# EPS.net
KiCad netlist of a schematic drawn in EAGLE
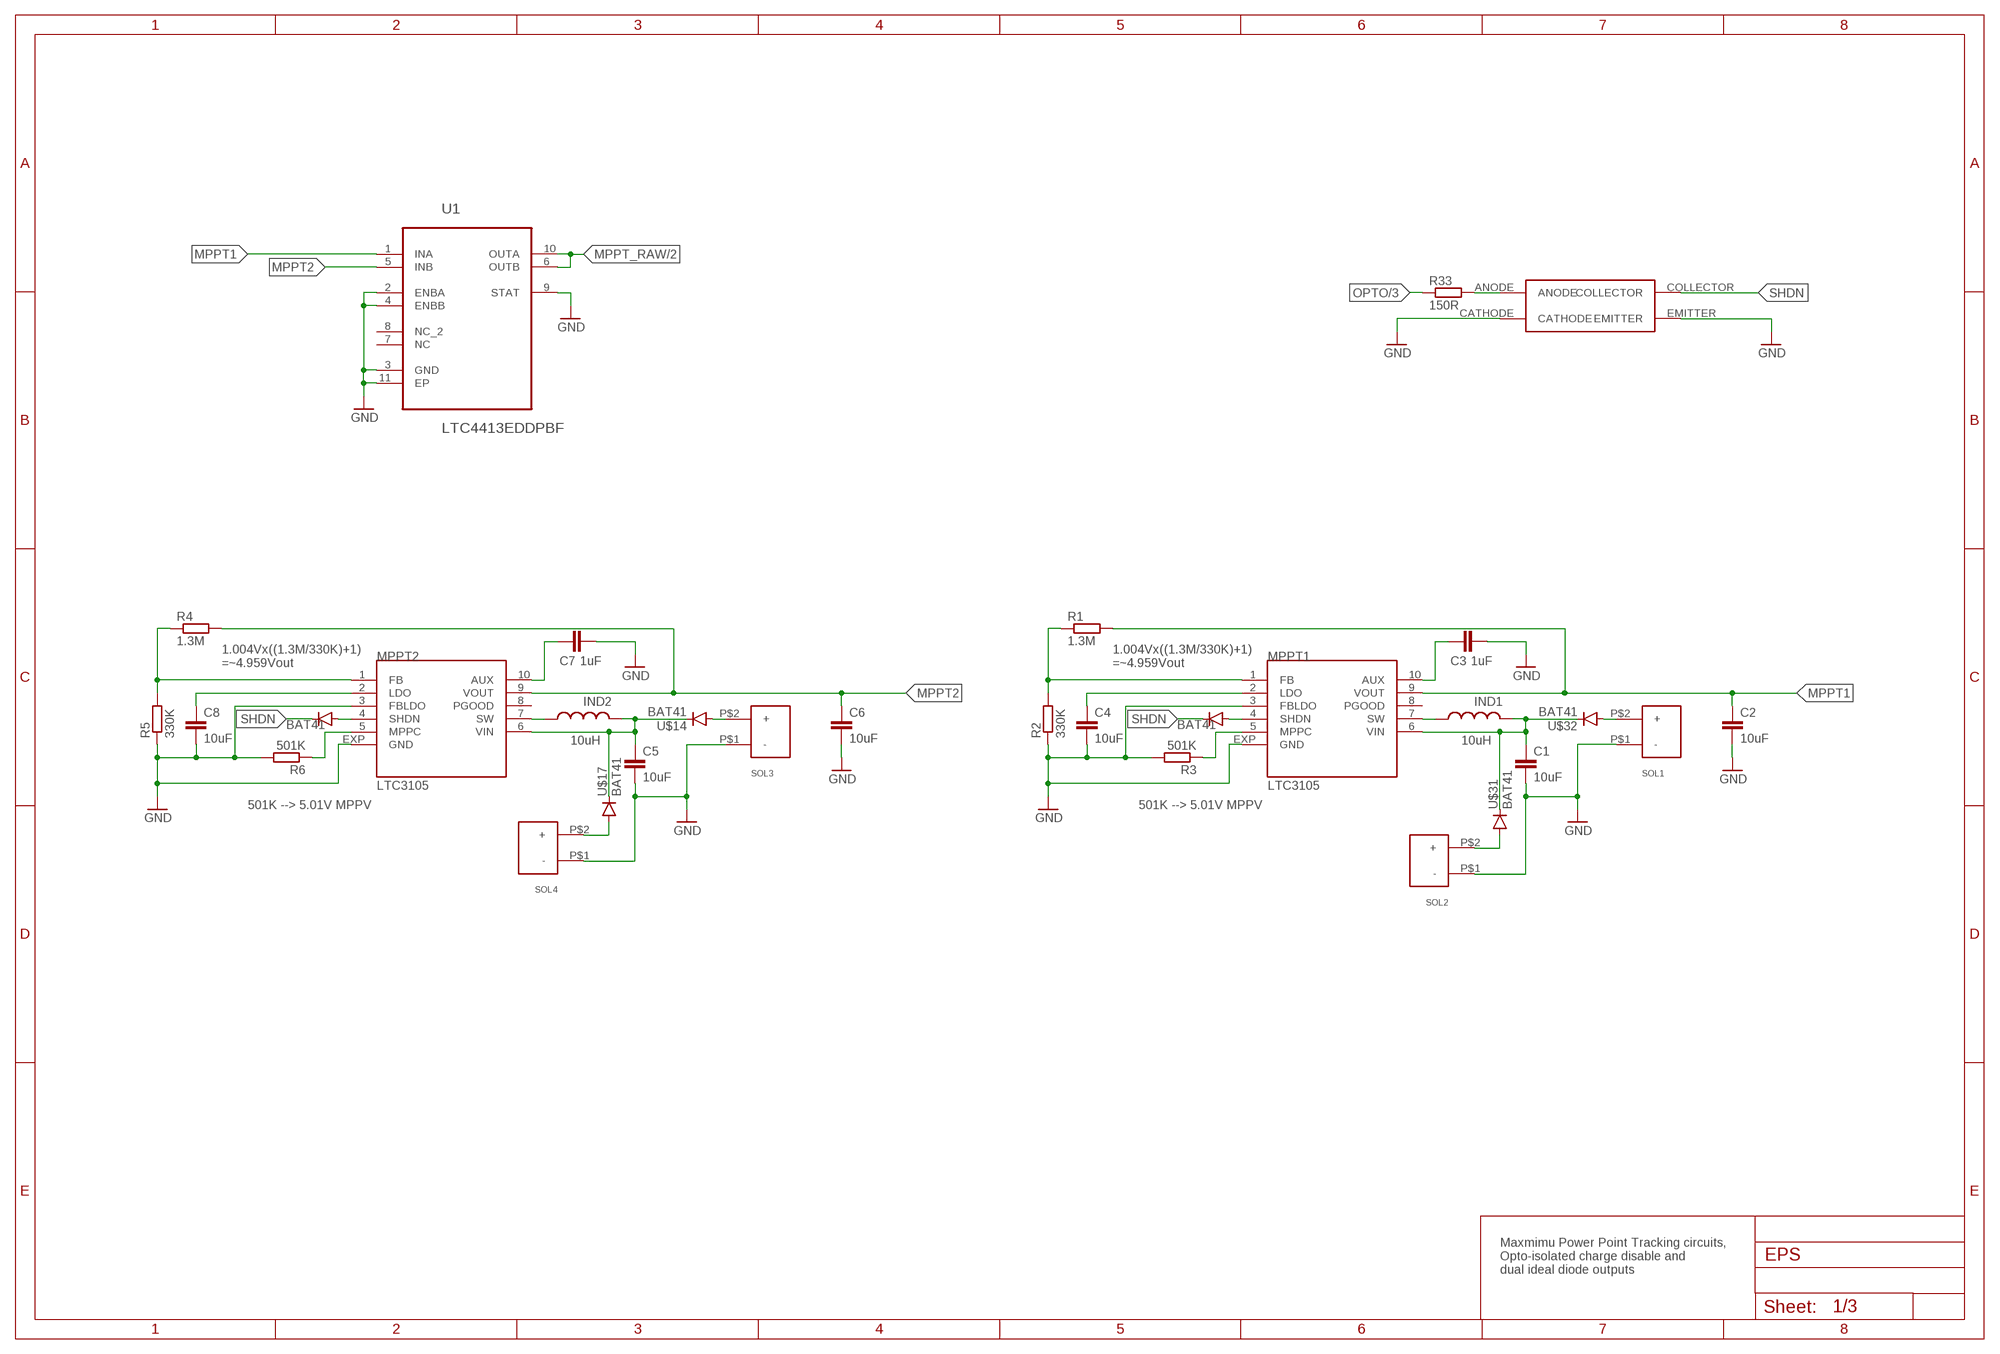
[diagram p0: schematic, sheet 1]
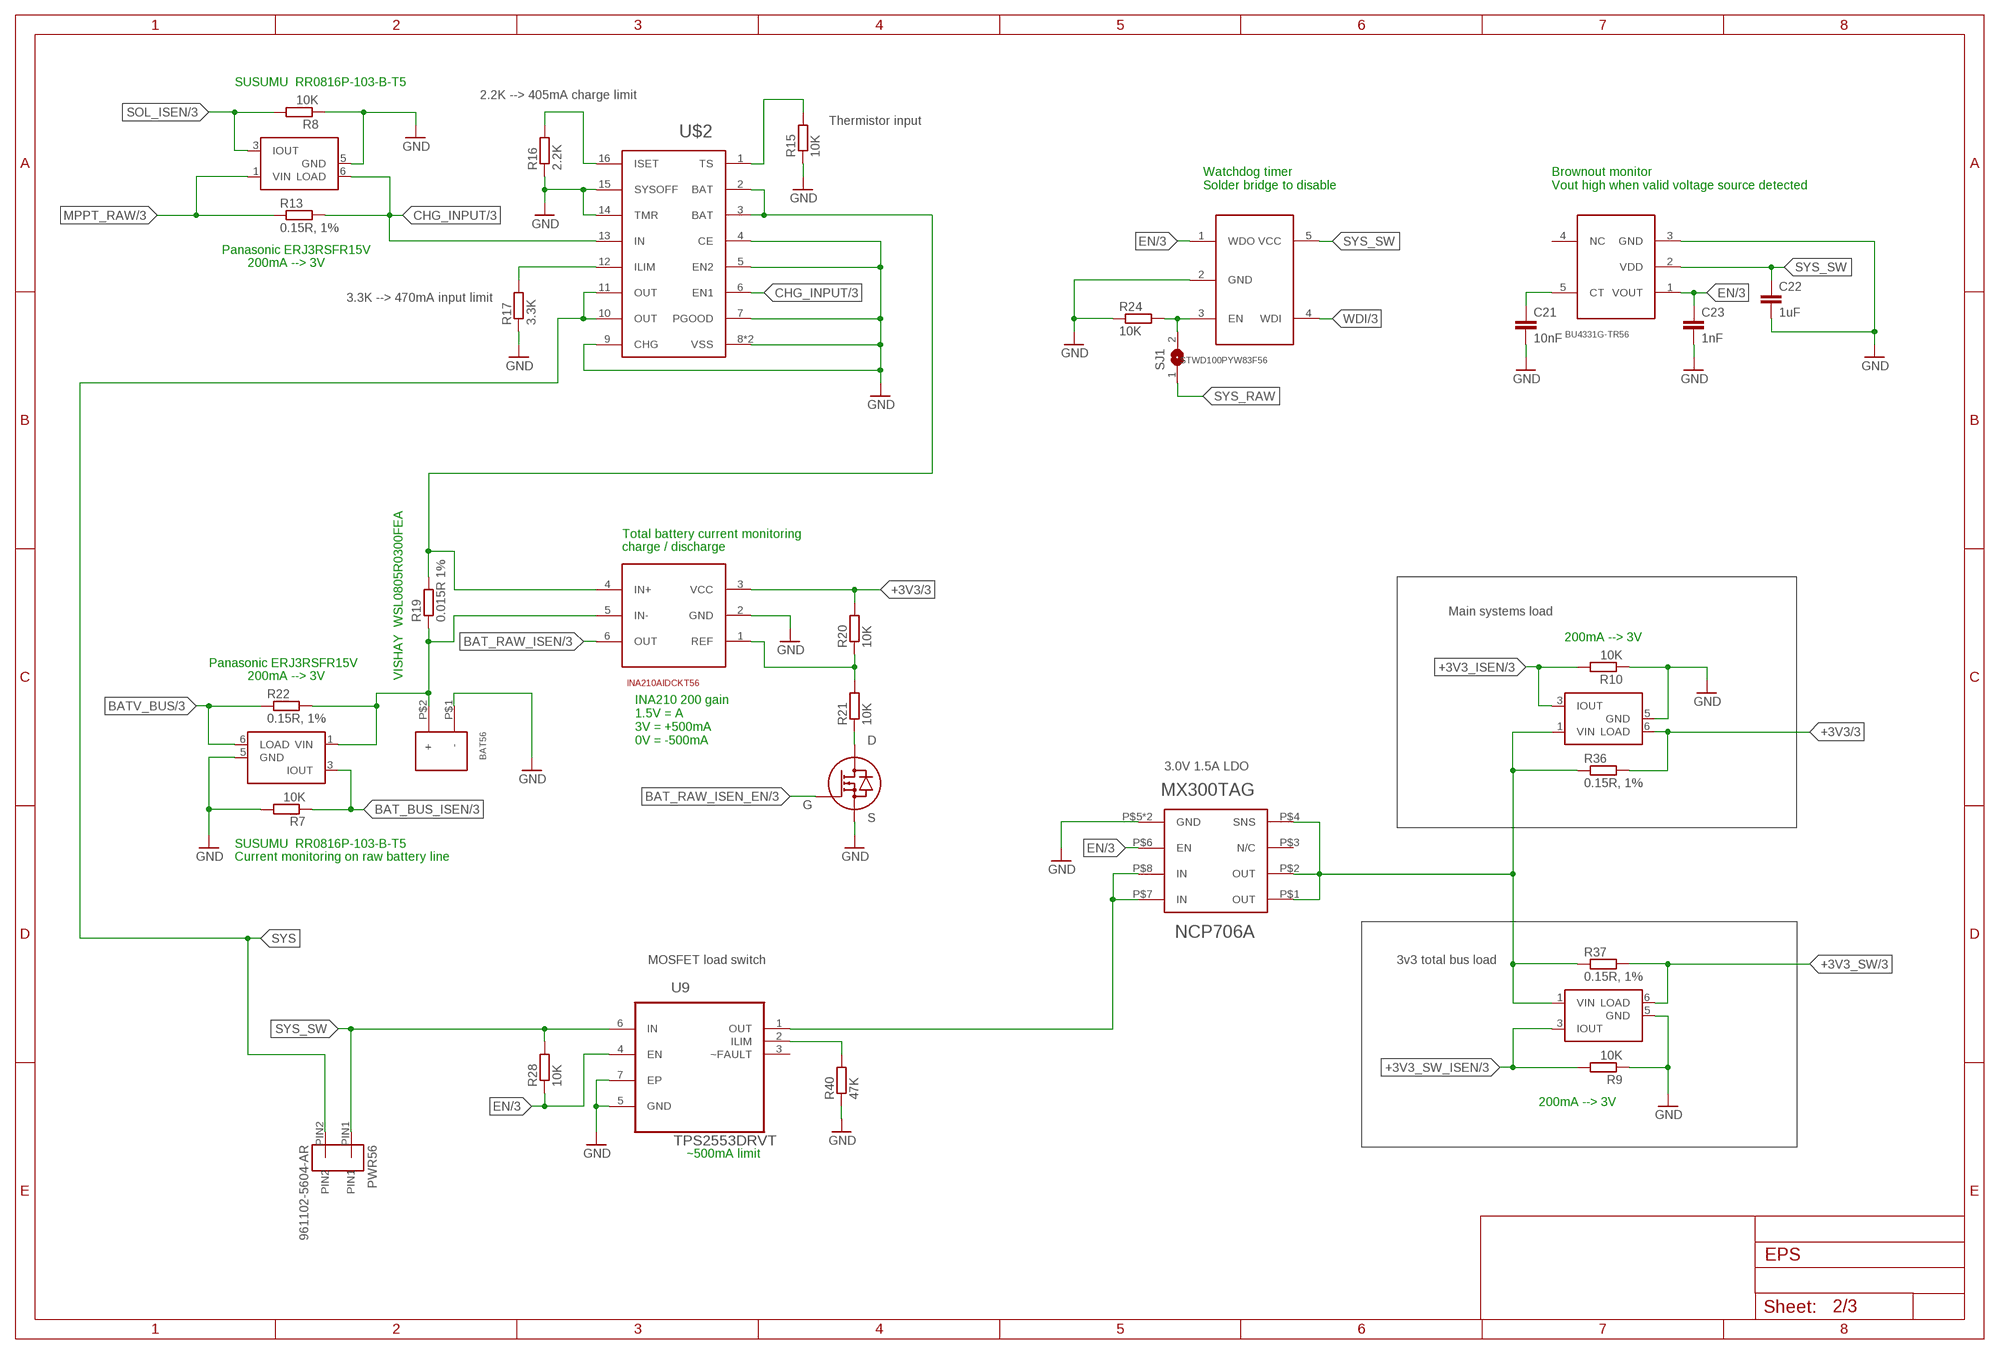
[diagram p1: schematic, sheet 2]
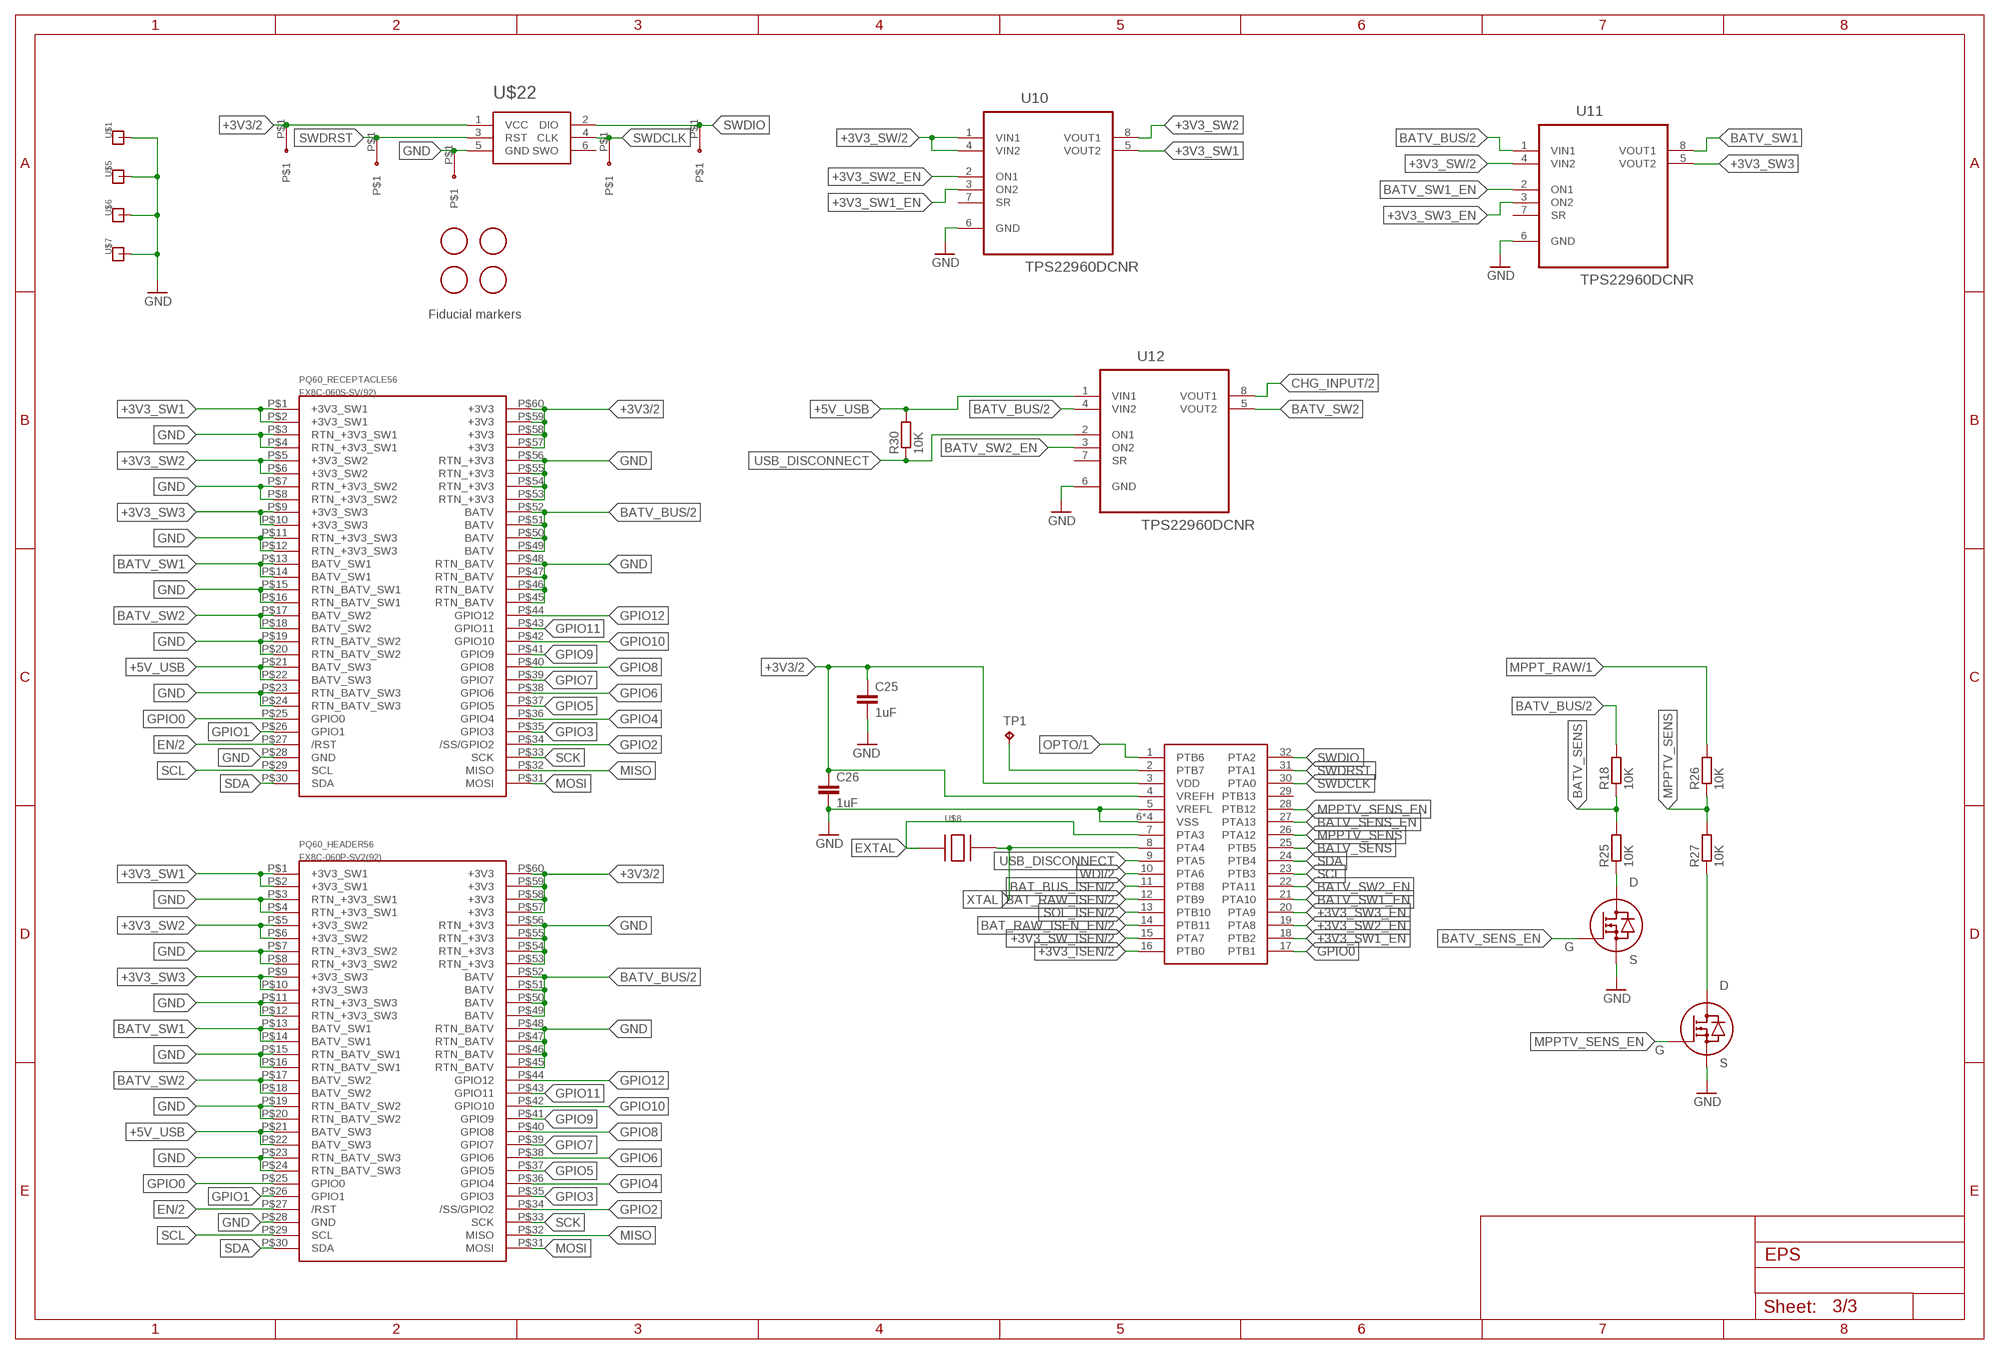
[diagram p2: schematic, sheet 3]

(export (version "E")
  (design (tool "Eeschema 10.0.6"))
  (components
    (comp (ref "C1")
      (value "10uF")
      (footprint "eagle-import:C0603")
      (libsource (lib "eagle-import") (part "C-EUC0603"))
    )
    (comp (ref "C2")
      (value "10uF")
      (footprint "eagle-import:C0603")
      (libsource (lib "eagle-import") (part "C-EUC0603"))
    )
    (comp (ref "C3")
      (value "1uF")
      (footprint "eagle-import:C0402")
      (libsource (lib "eagle-import") (part "C-EUC0402"))
    )
    (comp (ref "C4")
      (value "10uF")
      (footprint "eagle-import:C0603")
      (libsource (lib "eagle-import") (part "C-EUC0603"))
    )
    (comp (ref "C5")
      (value "10uF")
      (footprint "eagle-import:C0603")
      (libsource (lib "eagle-import") (part "C-EUC0603"))
    )
    (comp (ref "C6")
      (value "10uF")
      (footprint "eagle-import:C0603")
      (libsource (lib "eagle-import") (part "C-EUC0603"))
    )
    (comp (ref "C7")
      (value "1uF")
      (footprint "eagle-import:C0402")
      (libsource (lib "eagle-import") (part "C-EUC0402"))
    )
    (comp (ref "C8")
      (value "10uF")
      (footprint "eagle-import:C0603")
      (libsource (lib "eagle-import") (part "C-EUC0603"))
    )
    (comp (ref "IND1")
      (value "WE-TPC-744031100")
      (footprint "eagle-import:WE-TPC-744031100")
      (libsource (lib "eagle-import") (part "WE-TPC-744031100"))
    )
    (comp (ref "IND2")
      (value "WE-TPC-744031100")
      (footprint "eagle-import:WE-TPC-744031100")
      (libsource (lib "eagle-import") (part "WE-TPC-744031100"))
    )
    (comp (ref "MPPT1")
      (value "LTC3105")
      (footprint "eagle-import:DFN-3X3")
      (libsource (lib "eagle-import") (part "LTC3105"))
    )
    (comp (ref "MPPT2")
      (value "LTC3105")
      (footprint "eagle-import:DFN-3X3")
      (libsource (lib "eagle-import") (part "LTC3105"))
    )
    (comp (ref "R1")
      (value "1.3M")
      (footprint "eagle-import:R0402")
      (libsource (lib "eagle-import") (part "R-EU_R0402"))
    )
    (comp (ref "R2")
      (value "330K")
      (footprint "eagle-import:R0402")
      (libsource (lib "eagle-import") (part "R-EU_R0402"))
    )
    (comp (ref "R3")
      (value "501K")
      (footprint "eagle-import:R0402")
      (libsource (lib "eagle-import") (part "R-EU_R0402"))
    )
    (comp (ref "R4")
      (value "1.3M")
      (footprint "eagle-import:R0402")
      (libsource (lib "eagle-import") (part "R-EU_R0402"))
    )
    (comp (ref "R5")
      (value "330K")
      (footprint "eagle-import:R0402")
      (libsource (lib "eagle-import") (part "R-EU_R0402"))
    )
    (comp (ref "R6")
      (value "501K")
      (footprint "eagle-import:R0402")
      (libsource (lib "eagle-import") (part "R-EU_R0402"))
    )
    (comp (ref "R33")
      (value "150R")
      (footprint "eagle-import:R0402")
      (libsource (lib "eagle-import") (part "R-EU_R0402"))
    )
    (comp (ref "SOL1")
      (value "JST-B2B-ZH")
      (footprint "eagle-import:JST-B2B-ZR")
      (libsource (lib "eagle-import") (part "JST-B2B-ZH"))
    )
    (comp (ref "SOL2")
      (value "JST-B2B-ZH")
      (footprint "eagle-import:JST-B2B-ZR")
      (libsource (lib "eagle-import") (part "JST-B2B-ZH"))
    )
    (comp (ref "SOL3")
      (value "JST-B2B-ZH")
      (footprint "eagle-import:JST-B2B-ZR")
      (libsource (lib "eagle-import") (part "JST-B2B-ZH"))
    )
    (comp (ref "SOL4")
      (value "JST-B2B-ZH")
      (footprint "eagle-import:JST-B2B-ZR")
      (libsource (lib "eagle-import") (part "JST-B2B-ZH"))
    )
    (comp (ref "U$4")
      (value "BAT41")
      (footprint "eagle-import:SOD-123")
      (libsource (lib "eagle-import") (part "BAT41"))
    )
    (comp (ref "U$10")
      (value "BAT41")
      (footprint "eagle-import:SOD-123")
      (libsource (lib "eagle-import") (part "BAT41"))
    )
    (comp (ref "U$14")
      (value "BAT41")
      (footprint "eagle-import:SOD-123")
      (libsource (lib "eagle-import") (part "BAT41"))
    )
    (comp (ref "U$17")
      (value "BAT41")
      (footprint "eagle-import:SOD-123")
      (libsource (lib "eagle-import") (part "BAT41"))
    )
    (comp (ref "U$24")
      (value "EL3H7")
      (footprint "eagle-import:EL3H7")
      (libsource (lib "eagle-import") (part "EL3H7"))
    )
    (comp (ref "U$31")
      (value "BAT41")
      (footprint "eagle-import:SOD-123")
      (libsource (lib "eagle-import") (part "BAT41"))
    )
    (comp (ref "U$32")
      (value "BAT41")
      (footprint "eagle-import:SOD-123")
      (libsource (lib "eagle-import") (part "BAT41"))
    )
    (comp (ref "U1")
      (value "LTC4413EDDPBF")
      (footprint "eagle-import:DFN300X300X80-11N")
      (fields (field (name "MPN") "LTC4413EDD#PBF"))
      (libsource (lib "eagle-import") (part "LTC4413EDDPBF"))
    )
    (comp (ref "C25")
      (value "1uF")
      (footprint "eagle-import:C0402")
      (libsource (lib "eagle-import") (part "C-EUC0402"))
    )
    (comp (ref "C26")
      (value "1uF")
      (footprint "eagle-import:C0402")
      (libsource (lib "eagle-import") (part "C-EUC0402"))
    )
    (comp (ref "FD1")
      (value "FIDUCIAL")
      (footprint "eagle-import:FIDUCIAL_1MM")
      (libsource (lib "eagle-import") (part "FIDUCIAL"))
    )
    (comp (ref "FD2")
      (value "FIDUCIAL")
      (footprint "eagle-import:FIDUCIAL_1MM")
      (libsource (lib "eagle-import") (part "FIDUCIAL"))
    )
    (comp (ref "FD3")
      (value "FIDUCIAL")
      (footprint "eagle-import:FIDUCIAL_1MM")
      (libsource (lib "eagle-import") (part "FIDUCIAL"))
    )
    (comp (ref "FD4")
      (value "FIDUCIAL")
      (footprint "eagle-import:FIDUCIAL_1MM")
      (libsource (lib "eagle-import") (part "FIDUCIAL"))
    )
    (comp (ref "PQ60_HEADER56")
      (value "FX8C-060P-SV2(92)")
      (footprint "eagle-import:FX8C-060P-SV(92)")
      (libsource (lib "eagle-import") (part "FX8C-060P-SV2(92)"))
    )
    (comp (ref "PQ60_RECEPTACLE56")
      (value "FX8C-060S-SV(92)")
      (footprint "eagle-import:FX8C-060S-SV(92)")
      (libsource (lib "eagle-import") (part "FX8C-060S-SV(92)"))
    )
    (comp (ref "R18")
      (value "10K")
      (footprint "eagle-import:R0402")
      (libsource (lib "eagle-import") (part "R-EU_R0402"))
    )
    (comp (ref "R25")
      (value "10K")
      (footprint "eagle-import:R0402")
      (libsource (lib "eagle-import") (part "R-EU_R0402"))
    )
    (comp (ref "R26")
      (value "10K")
      (footprint "eagle-import:R0402")
      (libsource (lib "eagle-import") (part "R-EU_R0402"))
    )
    (comp (ref "R27")
      (value "10K")
      (footprint "eagle-import:R0402")
      (libsource (lib "eagle-import") (part "R-EU_R0402"))
    )
    (comp (ref "R30")
      (value "10K")
      (footprint "eagle-import:R0402")
      (libsource (lib "eagle-import") (part "R-EU_R0402"))
    )
    (comp (ref "TP1")
      (value "TPTP07R")
      (footprint "eagle-import:TP07R")
      (libsource (lib "eagle-import") (part "TPTP07R"))
    )
    (comp (ref "U$1")
      (value "3MMPILAR")
      (footprint "eagle-import:3MMPILAR")
      (libsource (lib "eagle-import") (part "3MMPILAR"))
    )
    (comp (ref "U$3")
      (value "DEBUG-TP")
      (footprint "eagle-import:DEBUG-TP")
      (libsource (lib "eagle-import") (part "DEBUG-TP"))
    )
    (comp (ref "U$5")
      (value "3MMPILAR")
      (footprint "eagle-import:3MMPILAR")
      (libsource (lib "eagle-import") (part "3MMPILAR"))
    )
    (comp (ref "U$6")
      (value "3MMPILAR")
      (footprint "eagle-import:3MMPILAR")
      (libsource (lib "eagle-import") (part "3MMPILAR"))
    )
    (comp (ref "U$7")
      (value "3MMPILAR")
      (footprint "eagle-import:3MMPILAR")
      (libsource (lib "eagle-import") (part "3MMPILAR"))
    )
    (comp (ref "U$8")
      (value "ABS25_32.768KHZ")
      (footprint "eagle-import:ABS25")
      (libsource (lib "eagle-import") (part "ABS25_32.768KHZ"))
    )
    (comp (ref "U$11")
      (value "PMV40UN2")
      (footprint "eagle-import:SOT23-3")
      (libsource (lib "eagle-import") (part "PMV40UN2"))
    )
    (comp (ref "U$12")
      (value "PMV40UN2")
      (footprint "eagle-import:SOT23-3")
      (libsource (lib "eagle-import") (part "PMV40UN2"))
    )
    (comp (ref "U$16")
      (value "DEBUG-TP")
      (footprint "eagle-import:DEBUG-TP")
      (libsource (lib "eagle-import") (part "DEBUG-TP"))
    )
    (comp (ref "U$21")
      (value "MKL02Z16VFM4")
      (footprint "eagle-import:MKL02Z16VFM4")
      (libsource (lib "eagle-import") (part "MKL02Z16VFM4"))
    )
    (comp (ref "U$22")
      (value "TAG_CONNECT")
      (footprint "eagle-import:TAG_CONNECT")
      (libsource (lib "eagle-import") (part "TAG_CONNECT"))
    )
    (comp (ref "U$23")
      (value "DEBUG-TP")
      (footprint "eagle-import:DEBUG-TP")
      (libsource (lib "eagle-import") (part "DEBUG-TP"))
    )
    (comp (ref "U$27")
      (value "DEBUG-TP")
      (footprint "eagle-import:DEBUG-TP")
      (libsource (lib "eagle-import") (part "DEBUG-TP"))
    )
    (comp (ref "U$28")
      (value "DEBUG-TP")
      (footprint "eagle-import:DEBUG-TP")
      (libsource (lib "eagle-import") (part "DEBUG-TP"))
    )
    (comp (ref "U10")
      (value "TPS22960DCNR")
      (footprint "eagle-import:SOT65P280X145-8N")
      (libsource (lib "eagle-import") (part "TPS22960DCNR"))
    )
    (comp (ref "U11")
      (value "TPS22960DCNR")
      (footprint "eagle-import:SOT65P280X145-8N")
      (libsource (lib "eagle-import") (part "TPS22960DCNR"))
    )
    (comp (ref "U12")
      (value "TPS22960DCNR")
      (footprint "eagle-import:SOT65P280X145-8N")
      (libsource (lib "eagle-import") (part "TPS22960DCNR"))
    )
    (comp (ref "BAT56")
      (value "JST-B2B-ZH")
      (footprint "eagle-import:JST-B2B-ZR")
      (libsource (lib "eagle-import") (part "JST-B2B-ZH"))
    )
    (comp (ref "BU4331G-TR56")
      (value "BU4231G-TR")
      (footprint "eagle-import:SSOP5")
      (libsource (lib "eagle-import") (part "BU4231G-TR"))
    )
    (comp (ref "C21")
      (value "10nF")
      (footprint "eagle-import:C0402")
      (libsource (lib "eagle-import") (part "C-EUC0402"))
    )
    (comp (ref "C22")
      (value "1uF")
      (footprint "eagle-import:C0402")
      (libsource (lib "eagle-import") (part "C-EUC0402"))
    )
    (comp (ref "C23")
      (value "1nF")
      (footprint "eagle-import:C0402")
      (libsource (lib "eagle-import") (part "C-EUC0402"))
    )
    (comp (ref "INA210AIDCKT56")
      (value "INA211A")
      (footprint "eagle-import:SC-70")
      (libsource (lib "eagle-import") (part "INA211A"))
    )
    (comp (ref "PWR56")
      (value "961102-5604-AR")
      (footprint "eagle-import:961102-5604-AR")
      (libsource (lib "eagle-import") (part "961102-5604-AR"))
    )
    (comp (ref "R7")
      (value "10K")
      (footprint "eagle-import:R0402")
      (libsource (lib "eagle-import") (part "R-EU_R0402"))
    )
    (comp (ref "R8")
      (value "10K")
      (footprint "eagle-import:R0402")
      (libsource (lib "eagle-import") (part "R-EU_R0402"))
    )
    (comp (ref "R9")
      (value "10K")
      (footprint "eagle-import:R0402")
      (libsource (lib "eagle-import") (part "R-EU_R0402"))
    )
    (comp (ref "R10")
      (value "10K")
      (footprint "eagle-import:R0402")
      (libsource (lib "eagle-import") (part "R-EU_R0402"))
    )
    (comp (ref "R13")
      (value "0.15R, 1%")
      (footprint "eagle-import:R0603")
      (libsource (lib "eagle-import") (part "R-EU_R0603"))
    )
    (comp (ref "R15")
      (value "10K")
      (footprint "eagle-import:R0402")
      (libsource (lib "eagle-import") (part "R-EU_R0402"))
    )
    (comp (ref "R16")
      (value "2.2K")
      (footprint "eagle-import:R0402")
      (libsource (lib "eagle-import") (part "R-EU_R0402"))
    )
    (comp (ref "R17")
      (value "3.3K")
      (footprint "eagle-import:R0402")
      (libsource (lib "eagle-import") (part "R-EU_R0402"))
    )
    (comp (ref "R19")
      (value "0.015R 1%")
      (footprint "eagle-import:R0603")
      (libsource (lib "eagle-import") (part "R-EU_R0603"))
    )
    (comp (ref "R20")
      (value "10K")
      (footprint "eagle-import:R0402")
      (libsource (lib "eagle-import") (part "R-EU_R0402"))
    )
    (comp (ref "R21")
      (value "10K")
      (footprint "eagle-import:R0402")
      (libsource (lib "eagle-import") (part "R-EU_R0402"))
    )
    (comp (ref "R22")
      (value "0.15R, 1%")
      (footprint "eagle-import:R0603")
      (libsource (lib "eagle-import") (part "R-EU_R0603"))
    )
    (comp (ref "R24")
      (value "10K")
      (footprint "eagle-import:R0402")
      (libsource (lib "eagle-import") (part "R-EU_R0402"))
    )
    (comp (ref "R28")
      (value "10K")
      (footprint "eagle-import:R0402")
      (libsource (lib "eagle-import") (part "R-EU_R0402"))
    )
    (comp (ref "R36")
      (value "0.15R, 1%")
      (footprint "eagle-import:R0603")
      (libsource (lib "eagle-import") (part "R-EU_R0603"))
    )
    (comp (ref "R37")
      (value "0.15R, 1%")
      (footprint "eagle-import:R0603")
      (libsource (lib "eagle-import") (part "R-EU_R0603"))
    )
    (comp (ref "R40")
      (value "47K")
      (footprint "eagle-import:R0402")
      (libsource (lib "eagle-import") (part "R-EU_R0402"))
    )
    (comp (ref "SJ1") (value "SJ") (footprint "eagle-import:SJ") (libsource (lib "eagle-import") (part "SJ")))
    (comp (ref "STWD100PYW83F56")
      (value "STWD100PYW83F")
      (footprint "eagle-import:SOT_323-5")
      (libsource (lib "eagle-import") (part "STWD100PYW83F"))
    )
    (comp (ref "U$2")
      (value "BQ24079")
      (footprint "eagle-import:PVQFN16-THERM")
      (libsource (lib "eagle-import") (part "BQ24079"))
    )
    (comp (ref "U$15")
      (value "PMV40UN2")
      (footprint "eagle-import:SOT23-3")
      (libsource (lib "eagle-import") (part "PMV40UN2"))
    )
    (comp (ref "U$18")
      (value "FAN4010IL6X_F113")
      (footprint "eagle-import:FAN4010IL6X_F113")
      (libsource (lib "eagle-import") (part "FAN4010IL6X_F113"))
    )
    (comp (ref "U$19")
      (value "FAN4010IL6X_F113")
      (footprint "eagle-import:FAN4010IL6X_F113")
      (libsource (lib "eagle-import") (part "FAN4010IL6X_F113"))
    )
    (comp (ref "U$20")
      (value "NCP706AMX300TAG")
      (footprint "eagle-import:XDFN8")
      (libsource (lib "eagle-import") (part "NCP706AMX300TAG"))
    )
    (comp (ref "U$25")
      (value "FAN4010IL6X_F113")
      (footprint "eagle-import:FAN4010IL6X_F113")
      (libsource (lib "eagle-import") (part "FAN4010IL6X_F113"))
    )
    (comp (ref "U$26")
      (value "FAN4010IL6X_F113")
      (footprint "eagle-import:FAN4010IL6X_F113")
      (libsource (lib "eagle-import") (part "FAN4010IL6X_F113"))
    )
    (comp (ref "U9")
      (value "TPS2553DRVT")
      (footprint "eagle-import:SON65P200X200X80-7N")
      (libsource (lib "eagle-import") (part "TPS2553DRVT"))
    )
  )
  (nets
    (net (code "1") (name "+3V3") (class "Default")
      (node (ref "C25") (pin "1") (pinfunction "1_1") (pintype "passive"))
      (node (ref "C26") (pin "1") (pinfunction "1_1") (pintype "passive"))
      (node (ref "INA210AIDCKT56") (pin "3") (pinfunction "VCC_3") (pintype "bidirectional"))
      (node (ref "PQ60_HEADER56") (pin "P$57") (pinfunction "+3V3_P$57") (pintype "power_in"))
      (node (ref "PQ60_HEADER56") (pin "P$58") (pinfunction "+3V3_P$58") (pintype "power_in"))
      (node (ref "PQ60_HEADER56") (pin "P$59") (pinfunction "+3V3_P$59") (pintype "power_in"))
      (node (ref "PQ60_HEADER56") (pin "P$60") (pinfunction "+3V3_P$60") (pintype "power_in"))
      (node (ref "PQ60_RECEPTACLE56") (pin "P$57") (pinfunction "+3V3_P$57") (pintype "power_in"))
      (node (ref "PQ60_RECEPTACLE56") (pin "P$58") (pinfunction "+3V3_P$58") (pintype "power_in"))
      (node (ref "PQ60_RECEPTACLE56") (pin "P$59") (pinfunction "+3V3_P$59") (pintype "power_in"))
      (node (ref "PQ60_RECEPTACLE56") (pin "P$60") (pinfunction "+3V3_P$60") (pintype "power_in"))
      (node (ref "R20") (pin "2") (pinfunction "2_2") (pintype "passive"))
      (node (ref "R36") (pin "2") (pinfunction "2_2") (pintype "passive"))
      (node (ref "U$21") (pin "3") (pinfunction "VDD_3") (pintype "bidirectional"))
      (node (ref "U$21") (pin "4") (pinfunction "VREFH_4") (pintype "bidirectional"))
      (node (ref "U$22") (pin "1") (pinfunction "VCC_1") (pintype "bidirectional"))
      (node (ref "U$25") (pin "6") (pinfunction "LOAD_6") (pintype "bidirectional"))
      (node (ref "U$3") (pin "P$1") (pinfunction "P$1_P$1") (pintype "bidirectional"))
    )
    (net (code "2") (name "+3V3_ISEN") (class "Default")
      (node (ref "R10") (pin "2") (pinfunction "2_2") (pintype "passive"))
      (node (ref "U$21") (pin "16") (pinfunction "PTB0_16") (pintype "bidirectional"))
      (node (ref "U$25") (pin "3") (pinfunction "IOUT_3") (pintype "bidirectional"))
    )
    (net (code "3") (name "+3V3_SW") (class "Default")
      (node (ref "R37") (pin "2") (pinfunction "2_2") (pintype "passive"))
      (node (ref "U$26") (pin "6") (pinfunction "LOAD_6") (pintype "bidirectional"))
      (node (ref "U10") (pin "1") (pinfunction "VIN1_1") (pintype "power_in"))
      (node (ref "U10") (pin "4") (pinfunction "VIN2_4") (pintype "power_in"))
      (node (ref "U11") (pin "4") (pinfunction "VIN2_4") (pintype "power_in"))
    )
    (net (code "4") (name "+3V3_SW1") (class "Default")
      (node (ref "PQ60_HEADER56") (pin "P$1") (pinfunction "+3V3_SW1_P$1") (pintype "power_in"))
      (node (ref "PQ60_HEADER56") (pin "P$2") (pinfunction "+3V3_SW1_P$2") (pintype "power_in"))
      (node (ref "PQ60_RECEPTACLE56") (pin "P$1") (pinfunction "+3V3_SW1_P$1") (pintype "power_in"))
      (node (ref "PQ60_RECEPTACLE56") (pin "P$2") (pinfunction "+3V3_SW1_P$2") (pintype "power_in"))
      (node (ref "U10") (pin "5") (pinfunction "VOUT2_5") (pintype "output"))
    )
    (net (code "5") (name "+3V3_SW1_EN") (class "Default")
      (node (ref "U$21") (pin "18") (pinfunction "PTB2_18") (pintype "bidirectional"))
      (node (ref "U10") (pin "3") (pinfunction "ON2_3") (pintype "input"))
    )
    (net (code "6") (name "+3V3_SW2") (class "Default")
      (node (ref "PQ60_HEADER56") (pin "P$5") (pinfunction "+3V3_SW2_P$5") (pintype "power_in"))
      (node (ref "PQ60_HEADER56") (pin "P$6") (pinfunction "+3V3_SW2_P$6") (pintype "power_in"))
      (node (ref "PQ60_RECEPTACLE56") (pin "P$5") (pinfunction "+3V3_SW2_P$5") (pintype "power_in"))
      (node (ref "PQ60_RECEPTACLE56") (pin "P$6") (pinfunction "+3V3_SW2_P$6") (pintype "power_in"))
      (node (ref "U10") (pin "8") (pinfunction "VOUT1_8") (pintype "output"))
    )
    (net (code "7") (name "+3V3_SW2_EN") (class "Default")
      (node (ref "U$21") (pin "19") (pinfunction "PTA8_19") (pintype "bidirectional"))
      (node (ref "U10") (pin "2") (pinfunction "ON1_2") (pintype "input"))
    )
    (net (code "8") (name "+3V3_SW3") (class "Default")
      (node (ref "PQ60_HEADER56") (pin "P$10") (pinfunction "+3V3_SW3_P$10") (pintype "power_in"))
      (node (ref "PQ60_HEADER56") (pin "P$9") (pinfunction "+3V3_SW3_P$9") (pintype "power_in"))
      (node (ref "PQ60_RECEPTACLE56") (pin "P$10") (pinfunction "+3V3_SW3_P$10") (pintype "power_in"))
      (node (ref "PQ60_RECEPTACLE56") (pin "P$9") (pinfunction "+3V3_SW3_P$9") (pintype "power_in"))
      (node (ref "U11") (pin "5") (pinfunction "VOUT2_5") (pintype "output"))
    )
    (net (code "9") (name "+3V3_SW3_EN") (class "Default")
      (node (ref "U$21") (pin "20") (pinfunction "PTA9_20") (pintype "bidirectional"))
      (node (ref "U11") (pin "3") (pinfunction "ON2_3") (pintype "input"))
    )
    (net (code "10") (name "+3V3_SW_ISEN") (class "Default")
      (node (ref "R9") (pin "2") (pinfunction "2_2") (pintype "passive"))
      (node (ref "U$21") (pin "15") (pinfunction "PTA7_15") (pintype "bidirectional"))
      (node (ref "U$26") (pin "3") (pinfunction "IOUT_3") (pintype "bidirectional"))
    )
    (net (code "11") (name "+5V_USB") (class "Default")
      (node (ref "PQ60_HEADER56") (pin "P$21") (pinfunction "BATV_SW3_P$21") (pintype "power_in"))
      (node (ref "PQ60_HEADER56") (pin "P$22") (pinfunction "BATV_SW3_P$22") (pintype "power_in"))
      (node (ref "PQ60_RECEPTACLE56") (pin "P$21") (pinfunction "BATV_SW3_P$21") (pintype "power_in"))
      (node (ref "PQ60_RECEPTACLE56") (pin "P$22") (pinfunction "BATV_SW3_P$22") (pintype "power_in"))
      (node (ref "R30") (pin "2") (pinfunction "2_2") (pintype "passive"))
      (node (ref "U12") (pin "1") (pinfunction "VIN1_1") (pintype "power_in"))
    )
    (net (code "12") (name "BATV_BUS") (class "Default")
      (node (ref "PQ60_HEADER56") (pin "P$49") (pinfunction "BATV_P$49") (pintype "power_in"))
      (node (ref "PQ60_HEADER56") (pin "P$50") (pinfunction "BATV_P$50") (pintype "power_in"))
      (node (ref "PQ60_HEADER56") (pin "P$51") (pinfunction "BATV_P$51") (pintype "power_in"))
      (node (ref "PQ60_HEADER56") (pin "P$52") (pinfunction "BATV_P$52") (pintype "power_in"))
      (node (ref "PQ60_RECEPTACLE56") (pin "P$49") (pinfunction "BATV_P$49") (pintype "power_in"))
      (node (ref "PQ60_RECEPTACLE56") (pin "P$50") (pinfunction "BATV_P$50") (pintype "power_in"))
      (node (ref "PQ60_RECEPTACLE56") (pin "P$51") (pinfunction "BATV_P$51") (pintype "power_in"))
      (node (ref "PQ60_RECEPTACLE56") (pin "P$52") (pinfunction "BATV_P$52") (pintype "power_in"))
      (node (ref "R18") (pin "2") (pinfunction "2_2") (pintype "passive"))
      (node (ref "R22") (pin "1") (pinfunction "1_1") (pintype "passive"))
      (node (ref "U$19") (pin "6") (pinfunction "LOAD_6") (pintype "bidirectional"))
      (node (ref "U11") (pin "1") (pinfunction "VIN1_1") (pintype "power_in"))
      (node (ref "U12") (pin "4") (pinfunction "VIN2_4") (pintype "power_in"))
    )
    (net (code "13") (name "BATV_SENS") (class "Default")
      (node (ref "R18") (pin "1") (pinfunction "1_1") (pintype "passive"))
      (node (ref "R25") (pin "2") (pinfunction "2_2") (pintype "passive"))
      (node (ref "U$21") (pin "25") (pinfunction "PTB5_25") (pintype "bidirectional"))
    )
    (net (code "14") (name "BATV_SENS_EN") (class "Default")
      (node (ref "U$11") (pin "1") (pinfunction "G_1") (pintype "bidirectional"))
      (node (ref "U$21") (pin "27") (pinfunction "PTA13_27") (pintype "bidirectional"))
    )
    (net (code "15") (name "BATV_SW1") (class "Default")
      (node (ref "PQ60_HEADER56") (pin "P$13") (pinfunction "BATV_SW1_P$13") (pintype "power_in"))
      (node (ref "PQ60_HEADER56") (pin "P$14") (pinfunction "BATV_SW1_P$14") (pintype "power_in"))
      (node (ref "PQ60_RECEPTACLE56") (pin "P$13") (pinfunction "BATV_SW1_P$13") (pintype "power_in"))
      (node (ref "PQ60_RECEPTACLE56") (pin "P$14") (pinfunction "BATV_SW1_P$14") (pintype "power_in"))
      (node (ref "U11") (pin "8") (pinfunction "VOUT1_8") (pintype "output"))
    )
    (net (code "16") (name "BATV_SW1_EN") (class "Default")
      (node (ref "U$21") (pin "21") (pinfunction "PTA10_21") (pintype "bidirectional"))
      (node (ref "U11") (pin "2") (pinfunction "ON1_2") (pintype "input"))
    )
    (net (code "17") (name "BATV_SW2") (class "Default")
      (node (ref "PQ60_HEADER56") (pin "P$17") (pinfunction "BATV_SW2_P$17") (pintype "power_in"))
      (node (ref "PQ60_HEADER56") (pin "P$18") (pinfunction "BATV_SW2_P$18") (pintype "power_in"))
      (node (ref "PQ60_RECEPTACLE56") (pin "P$17") (pinfunction "BATV_SW2_P$17") (pintype "power_in"))
      (node (ref "PQ60_RECEPTACLE56") (pin "P$18") (pinfunction "BATV_SW2_P$18") (pintype "power_in"))
      (node (ref "U12") (pin "5") (pinfunction "VOUT2_5") (pintype "output"))
    )
    (net (code "18") (name "BATV_SW2_EN") (class "Default")
      (node (ref "U$21") (pin "22") (pinfunction "PTA11_22") (pintype "bidirectional"))
      (node (ref "U12") (pin "3") (pinfunction "ON2_3") (pintype "input"))
    )
    (net (code "19") (name "BAT_BUS_ISEN") (class "Default")
      (node (ref "R7") (pin "1") (pinfunction "1_1") (pintype "passive"))
      (node (ref "U$19") (pin "3") (pinfunction "IOUT_3") (pintype "bidirectional"))
      (node (ref "U$21") (pin "11") (pinfunction "PTB8_11") (pintype "bidirectional"))
    )
    (net (code "20") (name "BAT_RAW_ISEN") (class "Default")
      (node (ref "INA210AIDCKT56") (pin "6") (pinfunction "OUT_6") (pintype "bidirectional"))
      (node (ref "U$21") (pin "12") (pinfunction "PTB9_12") (pintype "bidirectional"))
    )
    (net (code "21") (name "BAT_RAW_ISEN_EN") (class "Default")
      (node (ref "U$15") (pin "1") (pinfunction "G_1") (pintype "bidirectional"))
      (node (ref "U$21") (pin "14") (pinfunction "PTB11_14") (pintype "bidirectional"))
    )
    (net (code "22") (name "CHG_INPUT") (class "Default")
      (node (ref "R13") (pin "2") (pinfunction "2_2") (pintype "passive"))
      (node (ref "U$18") (pin "6") (pinfunction "LOAD_6") (pintype "bidirectional"))
      (node (ref "U$2") (pin "13") (pinfunction "IN_13") (pintype "bidirectional"))
      (node (ref "U$2") (pin "6") (pinfunction "EN1_6") (pintype "bidirectional"))
      (node (ref "U12") (pin "8") (pinfunction "VOUT1_8") (pintype "output"))
    )
    (net (code "23") (name "EN") (class "Default")
      (node (ref "BU4331G-TR56") (pin "1") (pinfunction "VOUT_1") (pintype "bidirectional"))
      (node (ref "C23") (pin "1") (pinfunction "1_1") (pintype "passive"))
      (node (ref "PQ60_HEADER56") (pin "P$27") (pinfunction "/RST_P$27") (pintype "bidirectional"))
      (node (ref "PQ60_RECEPTACLE56") (pin "P$27") (pinfunction "/RST_P$27") (pintype "bidirectional"))
      (node (ref "R28") (pin "1") (pinfunction "1_1") (pintype "passive"))
      (node (ref "STWD100PYW83F56") (pin "1") (pinfunction "WDO_1") (pintype "bidirectional"))
      (node (ref "U$20") (pin "P$6") (pinfunction "EN_P$6") (pintype "bidirectional"))
      (node (ref "U9") (pin "4") (pinfunction "EN_4") (pintype "input"))
    )
    (net (code "24") (name "EXTAL") (class "Default")
      (node (ref "U$21") (pin "7") (pinfunction "PTA3_7") (pintype "bidirectional"))
      (node (ref "U$8") (pin "1") (pinfunction "P$1_1") (pintype "bidirectional"))
    )
    (net (code "25") (name "GND") (class "Default")
      (node (ref "BAT56") (pin "P$1") (pinfunction "-_P$1") (pintype "bidirectional"))
      (node (ref "BU4331G-TR56") (pin "3") (pinfunction "GND_3") (pintype "bidirectional"))
      (node (ref "C1") (pin "2") (pinfunction "2_2") (pintype "passive"))
      (node (ref "C2") (pin "2") (pinfunction "2_2") (pintype "passive"))
      (node (ref "C21") (pin "2") (pinfunction "2_2") (pintype "passive"))
      (node (ref "C22") (pin "2") (pinfunction "2_2") (pintype "passive"))
      (node (ref "C23") (pin "2") (pinfunction "2_2") (pintype "passive"))
      (node (ref "C25") (pin "2") (pinfunction "2_2") (pintype "passive"))
      (node (ref "C26") (pin "2") (pinfunction "2_2") (pintype "passive"))
      (node (ref "C3") (pin "2") (pinfunction "2_2") (pintype "passive"))
      (node (ref "C4") (pin "2") (pinfunction "2_2") (pintype "passive"))
      (node (ref "C5") (pin "2") (pinfunction "2_2") (pintype "passive"))
      (node (ref "C6") (pin "2") (pinfunction "2_2") (pintype "passive"))
      (node (ref "C7") (pin "2") (pinfunction "2_2") (pintype "passive"))
      (node (ref "C8") (pin "2") (pinfunction "2_2") (pintype "passive"))
      (node (ref "INA210AIDCKT56") (pin "2") (pinfunction "GND_2") (pintype "bidirectional"))
      (node (ref "MPPT1") (pin "3") (pinfunction "FBLDO_3") (pintype "power_in"))
      (node (ref "MPPT1") (pin "EXP") (pinfunction "GND_EXP") (pintype "power_in"))
      (node (ref "MPPT2") (pin "3") (pinfunction "FBLDO_3") (pintype "power_in"))
      (node (ref "MPPT2") (pin "EXP") (pinfunction "GND_EXP") (pintype "power_in"))
      (node (ref "PQ60_HEADER56") (pin "P$11") (pinfunction "RTN_+3V3_SW3_P$11") (pintype "power_in"))
      (node (ref "PQ60_HEADER56") (pin "P$12") (pinfunction "RTN_+3V3_SW3_P$12") (pintype "power_in"))
      (node (ref "PQ60_HEADER56") (pin "P$15") (pinfunction "RTN_BATV_SW1_P$15") (pintype "power_in"))
      (node (ref "PQ60_HEADER56") (pin "P$16") (pinfunction "RTN_BATV_SW1_P$16") (pintype "power_in"))
      (node (ref "PQ60_HEADER56") (pin "P$19") (pinfunction "RTN_BATV_SW2_P$19") (pintype "power_in"))
      (node (ref "PQ60_HEADER56") (pin "P$20") (pinfunction "RTN_BATV_SW2_P$20") (pintype "power_in"))
      (node (ref "PQ60_HEADER56") (pin "P$23") (pinfunction "RTN_BATV_SW3_P$23") (pintype "power_in"))
      (node (ref "PQ60_HEADER56") (pin "P$24") (pinfunction "RTN_BATV_SW3_P$24") (pintype "power_in"))
      (node (ref "PQ60_HEADER56") (pin "P$28") (pinfunction "GND_P$28") (pintype "bidirectional"))
      (node (ref "PQ60_HEADER56") (pin "P$3") (pinfunction "RTN_+3V3_SW1_P$3") (pintype "power_in"))
      (node (ref "PQ60_HEADER56") (pin "P$4") (pinfunction "RTN_+3V3_SW1_P$4") (pintype "power_in"))
      (node (ref "PQ60_HEADER56") (pin "P$45") (pinfunction "RTN_BATV_P$45") (pintype "power_in"))
      (node (ref "PQ60_HEADER56") (pin "P$46") (pinfunction "RTN_BATV_P$46") (pintype "power_in"))
      (node (ref "PQ60_HEADER56") (pin "P$47") (pinfunction "RTN_BATV_P$47") (pintype "power_in"))
      (node (ref "PQ60_HEADER56") (pin "P$48") (pinfunction "RTN_BATV_P$48") (pintype "power_in"))
      (node (ref "PQ60_HEADER56") (pin "P$53") (pinfunction "RTN_+3V3_P$53") (pintype "power_in"))
      (node (ref "PQ60_HEADER56") (pin "P$54") (pinfunction "RTN_+3V3_P$54") (pintype "power_in"))
      (node (ref "PQ60_HEADER56") (pin "P$55") (pinfunction "RTN_+3V3_P$55") (pintype "power_in"))
      (node (ref "PQ60_HEADER56") (pin "P$56") (pinfunction "RTN_+3V3_P$56") (pintype "power_in"))
      (node (ref "PQ60_HEADER56") (pin "P$7") (pinfunction "RTN_+3V3_SW2_P$7") (pintype "power_in"))
      (node (ref "PQ60_HEADER56") (pin "P$8") (pinfunction "RTN_+3V3_SW2_P$8") (pintype "power_in"))
      (node (ref "PQ60_RECEPTACLE56") (pin "P$11") (pinfunction "RTN_+3V3_SW3_P$11") (pintype "power_in"))
      (node (ref "PQ60_RECEPTACLE56") (pin "P$12") (pinfunction "RTN_+3V3_SW3_P$12") (pintype "power_in"))
      (node (ref "PQ60_RECEPTACLE56") (pin "P$15") (pinfunction "RTN_BATV_SW1_P$15") (pintype "power_in"))
      (node (ref "PQ60_RECEPTACLE56") (pin "P$16") (pinfunction "RTN_BATV_SW1_P$16") (pintype "power_in"))
      (node (ref "PQ60_RECEPTACLE56") (pin "P$19") (pinfunction "RTN_BATV_SW2_P$19") (pintype "power_in"))
      (node (ref "PQ60_RECEPTACLE56") (pin "P$20") (pinfunction "RTN_BATV_SW2_P$20") (pintype "power_in"))
      (node (ref "PQ60_RECEPTACLE56") (pin "P$23") (pinfunction "RTN_BATV_SW3_P$23") (pintype "power_in"))
      (node (ref "PQ60_RECEPTACLE56") (pin "P$24") (pinfunction "RTN_BATV_SW3_P$24") (pintype "power_in"))
      (node (ref "PQ60_RECEPTACLE56") (pin "P$28") (pinfunction "GND_P$28") (pintype "bidirectional"))
      (node (ref "PQ60_RECEPTACLE56") (pin "P$3") (pinfunction "RTN_+3V3_SW1_P$3") (pintype "power_in"))
      (node (ref "PQ60_RECEPTACLE56") (pin "P$4") (pinfunction "RTN_+3V3_SW1_P$4") (pintype "power_in"))
      (node (ref "PQ60_RECEPTACLE56") (pin "P$45") (pinfunction "RTN_BATV_P$45") (pintype "power_in"))
      (node (ref "PQ60_RECEPTACLE56") (pin "P$46") (pinfunction "RTN_BATV_P$46") (pintype "power_in"))
      (node (ref "PQ60_RECEPTACLE56") (pin "P$47") (pinfunction "RTN_BATV_P$47") (pintype "power_in"))
      (node (ref "PQ60_RECEPTACLE56") (pin "P$48") (pinfunction "RTN_BATV_P$48") (pintype "power_in"))
      (node (ref "PQ60_RECEPTACLE56") (pin "P$53") (pinfunction "RTN_+3V3_P$53") (pintype "power_in"))
      (node (ref "PQ60_RECEPTACLE56") (pin "P$54") (pinfunction "RTN_+3V3_P$54") (pintype "power_in"))
      (node (ref "PQ60_RECEPTACLE56") (pin "P$55") (pinfunction "RTN_+3V3_P$55") (pintype "power_in"))
      (node (ref "PQ60_RECEPTACLE56") (pin "P$56") (pinfunction "RTN_+3V3_P$56") (pintype "power_in"))
      (node (ref "PQ60_RECEPTACLE56") (pin "P$7") (pinfunction "RTN_+3V3_SW2_P$7") (pintype "power_in"))
      (node (ref "PQ60_RECEPTACLE56") (pin "P$8") (pinfunction "RTN_+3V3_SW2_P$8") (pintype "power_in"))
      (node (ref "R10") (pin "1") (pinfunction "1_1") (pintype "passive"))
      (node (ref "R15") (pin "1") (pinfunction "1_1") (pintype "passive"))
      (node (ref "R16") (pin "1") (pinfunction "1_1") (pintype "passive"))
      (node (ref "R17") (pin "1") (pinfunction "1_1") (pintype "passive"))
      (node (ref "R2") (pin "1") (pinfunction "1_1") (pintype "passive"))
      (node (ref "R24") (pin "1") (pinfunction "1_1") (pintype "passive"))
      (node (ref "R3") (pin "2") (pinfunction "2_2") (pintype "passive"))
      (node (ref "R40") (pin "1") (pinfunction "1_1") (pintype "passive"))
      (node (ref "R5") (pin "1") (pinfunction "1_1") (pintype "passive"))
      (node (ref "R6") (pin "2") (pinfunction "2_2") (pintype "passive"))
      (node (ref "R7") (pin "2") (pinfunction "2_2") (pintype "passive"))
      (node (ref "R8") (pin "1") (pinfunction "1_1") (pintype "passive"))
      (node (ref "R9") (pin "1") (pinfunction "1_1") (pintype "passive"))
      (node (ref "SOL1") (pin "P$1") (pinfunction "-_P$1") (pintype "bidirectional"))
      (node (ref "SOL2") (pin "P$1") (pinfunction "-_P$1") (pintype "bidirectional"))
      (node (ref "SOL3") (pin "P$1") (pinfunction "-_P$1") (pintype "bidirectional"))
      (node (ref "SOL4") (pin "P$1") (pinfunction "-_P$1") (pintype "bidirectional"))
      (node (ref "STWD100PYW83F56") (pin "2") (pinfunction "GND_2") (pintype "bidirectional"))
      (node (ref "U$1") (pin "P$1") (pinfunction "P$1_P$1") (pintype "bidirectional"))
      (node (ref "U$11") (pin "2") (pinfunction "S_2") (pintype "bidirectional"))
      (node (ref "U$12") (pin "2") (pinfunction "S_2") (pintype "bidirectional"))
      (node (ref "U$15") (pin "2") (pinfunction "S_2") (pintype "bidirectional"))
      (node (ref "U$18") (pin "5") (pinfunction "GND_5") (pintype "bidirectional"))
      (node (ref "U$19") (pin "5") (pinfunction "GND_5") (pintype "bidirectional"))
      (node (ref "U$2") (pin "14") (pinfunction "TMR_14") (pintype "bidirectional"))
      (node (ref "U$2") (pin "15") (pinfunction "SYSOFF_15") (pintype "bidirectional"))
      (node (ref "U$2") (pin "17") (pinfunction "VSS_17") (pintype "bidirectional"))
      (node (ref "U$2") (pin "4") (pinfunction "CE_4") (pintype "bidirectional"))
      (node (ref "U$2") (pin "5") (pinfunction "EN2_5") (pintype "bidirectional"))
      (node (ref "U$2") (pin "7") (pinfunction "PGOOD_7") (pintype "bidirectional"))
      (node (ref "U$2") (pin "8") (pinfunction "VSS_8") (pintype "bidirectional"))
      (node (ref "U$2") (pin "9") (pinfunction "CHG_9") (pintype "bidirectional"))
      (node (ref "U$20") (pin "P$5") (pinfunction "GND_P$5") (pintype "bidirectional"))
      (node (ref "U$20") (pin "P$9") (pinfunction "GND_P$9") (pintype "bidirectional"))
      (node (ref "U$21") (pin "5") (pinfunction "VREFL_5") (pintype "bidirectional"))
      (node (ref "U$21") (pin "6") (pinfunction "VSS_6") (pintype "bidirectional"))
      (node (ref "U$21") (pin "GND@1") (pinfunction "VSS_GND@1") (pintype "bidirectional"))
      (node (ref "U$21") (pin "GND@2") (pinfunction "VSS_GND@2") (pintype "bidirectional"))
      (node (ref "U$21") (pin "GND@3") (pinfunction "VSS_GND@3") (pintype "bidirectional"))
      (node (ref "U$22") (pin "5") (pinfunction "GND_5") (pintype "bidirectional"))
      (node (ref "U$23") (pin "P$1") (pinfunction "P$1_P$1") (pintype "bidirectional"))
      (node (ref "U$24") (pin "CATHODE") (pinfunction "CATHODE_CATHODE") (pintype "bidirectional"))
      (node (ref "U$24") (pin "EMITTER") (pinfunction "EMITTER_EMITTER") (pintype "bidirectional"))
      (node (ref "U$25") (pin "5") (pinfunction "GND_5") (pintype "bidirectional"))
      (node (ref "U$26") (pin "5") (pinfunction "GND_5") (pintype "bidirectional"))
      (node (ref "U$5") (pin "P$1") (pinfunction "P$1_P$1") (pintype "bidirectional"))
      (node (ref "U$6") (pin "P$1") (pinfunction "P$1_P$1") (pintype "bidirectional"))
      (node (ref "U$7") (pin "P$1") (pinfunction "P$1_P$1") (pintype "bidirectional"))
      (node (ref "U1") (pin "11") (pinfunction "EP_11") (pintype "passive"))
      (node (ref "U1") (pin "2") (pinfunction "ENBA_2") (pintype "input"))
      (node (ref "U1") (pin "3") (pinfunction "GND_3") (pintype "passive"))
      (node (ref "U1") (pin "4") (pinfunction "ENBB_4") (pintype "input"))
      (node (ref "U1") (pin "9") (pinfunction "STAT_9") (pintype "output"))
      (node (ref "U10") (pin "6") (pinfunction "GND_6") (pintype "passive"))
      (node (ref "U11") (pin "6") (pinfunction "GND_6") (pintype "passive"))
      (node (ref "U12") (pin "6") (pinfunction "GND_6") (pintype "passive"))
      (node (ref "U9") (pin "5") (pinfunction "GND_5") (pintype "passive"))
      (node (ref "U9") (pin "7") (pinfunction "EP_7") (pintype "passive"))
    )
    (net (code "26") (name "GPIO0") (class "Default")
      (node (ref "PQ60_HEADER56") (pin "P$25") (pinfunction "GPIO0_P$25") (pintype "bidirectional"))
      (node (ref "PQ60_RECEPTACLE56") (pin "P$25") (pinfunction "GPIO0_P$25") (pintype "bidirectional"))
      (node (ref "U$21") (pin "17") (pinfunction "PTB1_17") (pintype "bidirectional"))
    )
    (net (code "27") (name "GPIO1") (class "Default")
      (node (ref "PQ60_HEADER56") (pin "P$26") (pinfunction "GPIO1_P$26") (pintype "bidirectional"))
      (node (ref "PQ60_RECEPTACLE56") (pin "P$26") (pinfunction "GPIO1_P$26") (pintype "bidirectional"))
    )
    (net (code "28") (name "GPIO2") (class "Default")
      (node (ref "PQ60_HEADER56") (pin "P$34") (pinfunction "/SS/GPIO2_P$34") (pintype "bidirectional"))
      (node (ref "PQ60_RECEPTACLE56") (pin "P$34") (pinfunction "/SS/GPIO2_P$34") (pintype "bidirectional"))
    )
    (net (code "29") (name "GPIO3") (class "Default")
      (node (ref "PQ60_HEADER56") (pin "P$35") (pinfunction "GPIO3_P$35") (pintype "bidirectional"))
      (node (ref "PQ60_RECEPTACLE56") (pin "P$35") (pinfunction "GPIO3_P$35") (pintype "bidirectional"))
    )
    (net (code "30") (name "GPIO4") (class "Default")
      (node (ref "PQ60_HEADER56") (pin "P$36") (pinfunction "GPIO4_P$36") (pintype "bidirectional"))
      (node (ref "PQ60_RECEPTACLE56") (pin "P$36") (pinfunction "GPIO4_P$36") (pintype "bidirectional"))
    )
    (net (code "31") (name "GPIO5") (class "Default")
      (node (ref "PQ60_HEADER56") (pin "P$37") (pinfunction "GPIO5_P$37") (pintype "bidirectional"))
      (node (ref "PQ60_RECEPTACLE56") (pin "P$37") (pinfunction "GPIO5_P$37") (pintype "bidirectional"))
    )
    (net (code "32") (name "GPIO6") (class "Default")
      (node (ref "PQ60_HEADER56") (pin "P$38") (pinfunction "GPIO6_P$38") (pintype "bidirectional"))
      (node (ref "PQ60_RECEPTACLE56") (pin "P$38") (pinfunction "GPIO6_P$38") (pintype "bidirectional"))
    )
    (net (code "33") (name "GPIO7") (class "Default")
      (node (ref "PQ60_HEADER56") (pin "P$39") (pinfunction "GPIO7_P$39") (pintype "bidirectional"))
      (node (ref "PQ60_RECEPTACLE56") (pin "P$39") (pinfunction "GPIO7_P$39") (pintype "bidirectional"))
    )
    (net (code "34") (name "GPIO8") (class "Default")
      (node (ref "PQ60_HEADER56") (pin "P$40") (pinfunction "GPIO8_P$40") (pintype "bidirectional"))
      (node (ref "PQ60_RECEPTACLE56") (pin "P$40") (pinfunction "GPIO8_P$40") (pintype "bidirectional"))
    )
    (net (code "35") (name "GPIO9") (class "Default")
      (node (ref "PQ60_HEADER56") (pin "P$41") (pinfunction "GPIO9_P$41") (pintype "bidirectional"))
      (node (ref "PQ60_RECEPTACLE56") (pin "P$41") (pinfunction "GPIO9_P$41") (pintype "bidirectional"))
    )
    (net (code "36") (name "GPIO10") (class "Default")
      (node (ref "PQ60_HEADER56") (pin "P$42") (pinfunction "GPIO10_P$42") (pintype "bidirectional"))
      (node (ref "PQ60_RECEPTACLE56") (pin "P$42") (pinfunction "GPIO10_P$42") (pintype "bidirectional"))
    )
    (net (code "37") (name "GPIO11") (class "Default")
      (node (ref "PQ60_HEADER56") (pin "P$43") (pinfunction "GPIO11_P$43") (pintype "bidirectional"))
      (node (ref "PQ60_RECEPTACLE56") (pin "P$43") (pinfunction "GPIO11_P$43") (pintype "bidirectional"))
    )
    (net (code "38") (name "GPIO12") (class "Default")
      (node (ref "PQ60_HEADER56") (pin "P$44") (pinfunction "GPIO12_P$44") (pintype "bidirectional"))
      (node (ref "PQ60_RECEPTACLE56") (pin "P$44") (pinfunction "GPIO12_P$44") (pintype "bidirectional"))
    )
    (net (code "39") (name "MISO") (class "Default")
      (node (ref "PQ60_HEADER56") (pin "P$32") (pinfunction "MISO_P$32") (pintype "bidirectional"))
      (node (ref "PQ60_RECEPTACLE56") (pin "P$32") (pinfunction "MISO_P$32") (pintype "bidirectional"))
    )
    (net (code "40") (name "MOSI") (class "Default")
      (node (ref "PQ60_HEADER56") (pin "P$31") (pinfunction "MOSI_P$31") (pintype "bidirectional"))
      (node (ref "PQ60_RECEPTACLE56") (pin "P$31") (pinfunction "MOSI_P$31") (pintype "bidirectional"))
    )
    (net (code "41") (name "MPPT1") (class "Default")
      (node (ref "C2") (pin "1") (pinfunction "1_1") (pintype "passive"))
      (node (ref "MPPT1") (pin "9") (pinfunction "VOUT_9") (pintype "passive"))
      (node (ref "R1") (pin "2") (pinfunction "2_2") (pintype "passive"))
      (node (ref "U1") (pin "1") (pinfunction "INA_1") (pintype "power_in"))
    )
    (net (code "42") (name "MPPT2") (class "Default")
      (node (ref "C6") (pin "1") (pinfunction "1_1") (pintype "passive"))
      (node (ref "MPPT2") (pin "9") (pinfunction "VOUT_9") (pintype "passive"))
      (node (ref "R4") (pin "2") (pinfunction "2_2") (pintype "passive"))
      (node (ref "U1") (pin "5") (pinfunction "INB_5") (pintype "power_in"))
    )
    (net (code "43") (name "MPPTV_SENS") (class "Default")
      (node (ref "R26") (pin "1") (pinfunction "1_1") (pintype "passive"))
      (node (ref "R27") (pin "2") (pinfunction "2_2") (pintype "passive"))
      (node (ref "U$21") (pin "26") (pinfunction "PTA12_26") (pintype "bidirectional"))
    )
    (net (code "44") (name "MPPTV_SENS_EN") (class "Default")
      (node (ref "U$12") (pin "1") (pinfunction "G_1") (pintype "bidirectional"))
      (node (ref "U$21") (pin "28") (pinfunction "PTB12_28") (pintype "bidirectional"))
    )
    (net (code "45") (name "MPPT_RAW") (class "Default")
      (node (ref "R13") (pin "1") (pinfunction "1_1") (pintype "passive"))
      (node (ref "R26") (pin "2") (pinfunction "2_2") (pintype "passive"))
      (node (ref "U$18") (pin "1") (pinfunction "VIN_1") (pintype "bidirectional"))
      (node (ref "U1") (pin "10") (pinfunction "OUTA_10") (pintype "output"))
      (node (ref "U1") (pin "6") (pinfunction "OUTB_6") (pintype "output"))
    )
    (net (code "46") (name "Net-(BAT56-+)") (class "Default")
      (node (ref "BAT56") (pin "P$2") (pinfunction "+_P$2") (pintype "bidirectional"))
      (node (ref "INA210AIDCKT56") (pin "5") (pinfunction "IN-_5") (pintype "bidirectional"))
      (node (ref "R19") (pin "1") (pinfunction "1_1") (pintype "passive"))
      (node (ref "R22") (pin "2") (pinfunction "2_2") (pintype "passive"))
      (node (ref "U$19") (pin "1") (pinfunction "VIN_1") (pintype "bidirectional"))
    )
    (net (code "47") (name "Net-(BU4331G-TR56-CT)") (class "Default")
      (node (ref "BU4331G-TR56") (pin "5") (pinfunction "CT_5") (pintype "bidirectional"))
      (node (ref "C21") (pin "1") (pinfunction "1_1") (pintype "passive"))
    )
    (net (code "48") (name "Net-(INA210AIDCKT56-IN+)") (class "Default")
      (node (ref "INA210AIDCKT56") (pin "4") (pinfunction "IN+_4") (pintype "bidirectional"))
      (node (ref "R19") (pin "2") (pinfunction "2_2") (pintype "passive"))
      (node (ref "U$2") (pin "2") (pinfunction "BAT_2") (pintype "bidirectional"))
      (node (ref "U$2") (pin "3") (pinfunction "BAT_3") (pintype "bidirectional"))
    )
    (net (code "49") (name "Net-(INA210AIDCKT56-REF)") (class "Default")
      (node (ref "INA210AIDCKT56") (pin "1") (pinfunction "REF_1") (pintype "bidirectional"))
      (node (ref "R20") (pin "1") (pinfunction "1_1") (pintype "passive"))
      (node (ref "R21") (pin "2") (pinfunction "2_2") (pintype "passive"))
    )
    (net (code "50") (name "Net-(IND1-1)") (class "Default")
      (node (ref "IND1") (pin "P$1") (pinfunction "1_P$1") (pintype "passive"))
      (node (ref "MPPT1") (pin "7") (pinfunction "SW_7") (pintype "passive"))
    )
    (net (code "51") (name "Net-(IND1-2)") (class "Default")
      (node (ref "C1") (pin "1") (pinfunction "1_1") (pintype "passive"))
      (node (ref "IND1") (pin "P$3") (pinfunction "2_P$3") (pintype "passive"))
      (node (ref "MPPT1") (pin "6") (pinfunction "VIN_6") (pintype "input"))
      (node (ref "U$31") (pin "P$1") (pinfunction "C_P$1") (pintype "passive"))
      (node (ref "U$32") (pin "P$1") (pinfunction "C_P$1") (pintype "passive"))
    )
    (net (code "52") (name "Net-(IND2-1)") (class "Default")
      (node (ref "IND2") (pin "P$1") (pinfunction "1_P$1") (pintype "passive"))
      (node (ref "MPPT2") (pin "7") (pinfunction "SW_7") (pintype "passive"))
    )
    (net (code "53") (name "Net-(IND2-2)") (class "Default")
      (node (ref "C5") (pin "1") (pinfunction "1_1") (pintype "passive"))
      (node (ref "IND2") (pin "P$3") (pinfunction "2_P$3") (pintype "passive"))
      (node (ref "MPPT2") (pin "6") (pinfunction "VIN_6") (pintype "input"))
      (node (ref "U$14") (pin "P$1") (pinfunction "C_P$1") (pintype "passive"))
      (node (ref "U$17") (pin "P$1") (pinfunction "C_P$1") (pintype "passive"))
    )
    (net (code "54") (name "Net-(MPPT1-AUX)") (class "Default")
      (node (ref "C3") (pin "1") (pinfunction "1_1") (pintype "passive"))
      (node (ref "MPPT1") (pin "10") (pinfunction "AUX_10") (pintype "passive"))
    )
    (net (code "55") (name "Net-(MPPT1-FB)") (class "Default")
      (node (ref "MPPT1") (pin "1") (pinfunction "FB_1") (pintype "passive"))
      (node (ref "R1") (pin "1") (pinfunction "1_1") (pintype "passive"))
      (node (ref "R2") (pin "2") (pinfunction "2_2") (pintype "passive"))
    )
    (net (code "56") (name "Net-(MPPT1-LDO)") (class "Default")
      (node (ref "C4") (pin "1") (pinfunction "1_1") (pintype "passive"))
      (node (ref "MPPT1") (pin "2") (pinfunction "LDO_2") (pintype "passive"))
    )
    (net (code "57") (name "Net-(MPPT1-MPPC)") (class "Default")
      (node (ref "MPPT1") (pin "5") (pinfunction "MPPC_5") (pintype "input"))
      (node (ref "R3") (pin "1") (pinfunction "1_1") (pintype "passive"))
    )
    (net (code "58") (name "Net-(MPPT1-SHDN)") (class "Default")
      (node (ref "MPPT1") (pin "4") (pinfunction "SHDN_4") (pintype "input"))
      (node (ref "U$4") (pin "P$2") (pinfunction "A_P$2") (pintype "passive"))
    )
    (net (code "59") (name "Net-(MPPT2-AUX)") (class "Default")
      (node (ref "C7") (pin "1") (pinfunction "1_1") (pintype "passive"))
      (node (ref "MPPT2") (pin "10") (pinfunction "AUX_10") (pintype "passive"))
    )
    (net (code "60") (name "Net-(MPPT2-FB)") (class "Default")
      (node (ref "MPPT2") (pin "1") (pinfunction "FB_1") (pintype "passive"))
      (node (ref "R4") (pin "1") (pinfunction "1_1") (pintype "passive"))
      (node (ref "R5") (pin "2") (pinfunction "2_2") (pintype "passive"))
    )
    (net (code "61") (name "Net-(MPPT2-LDO)") (class "Default")
      (node (ref "C8") (pin "1") (pinfunction "1_1") (pintype "passive"))
      (node (ref "MPPT2") (pin "2") (pinfunction "LDO_2") (pintype "passive"))
    )
    (net (code "62") (name "Net-(MPPT2-MPPC)") (class "Default")
      (node (ref "MPPT2") (pin "5") (pinfunction "MPPC_5") (pintype "input"))
      (node (ref "R6") (pin "1") (pinfunction "1_1") (pintype "passive"))
    )
    (net (code "63") (name "Net-(MPPT2-SHDN)") (class "Default")
      (node (ref "MPPT2") (pin "4") (pinfunction "SHDN_4") (pintype "input"))
      (node (ref "U$10") (pin "P$2") (pinfunction "A_P$2") (pintype "passive"))
    )
    (net (code "64") (name "Net-(R33-Pad2)") (class "Default")
      (node (ref "R33") (pin "2") (pinfunction "2_2") (pintype "passive"))
      (node (ref "U$24") (pin "ANODE") (pinfunction "ANODE_ANODE") (pintype "bidirectional"))
    )
    (net (code "65") (name "Net-(SOL1-+)") (class "Default")
      (node (ref "SOL1") (pin "P$2") (pinfunction "+_P$2") (pintype "bidirectional"))
      (node (ref "U$32") (pin "P$2") (pinfunction "A_P$2") (pintype "passive"))
    )
    (net (code "66") (name "Net-(SOL2-+)") (class "Default")
      (node (ref "SOL2") (pin "P$2") (pinfunction "+_P$2") (pintype "bidirectional"))
      (node (ref "U$31") (pin "P$2") (pinfunction "A_P$2") (pintype "passive"))
    )
    (net (code "67") (name "Net-(SOL3-+)") (class "Default")
      (node (ref "SOL3") (pin "P$2") (pinfunction "+_P$2") (pintype "bidirectional"))
      (node (ref "U$14") (pin "P$2") (pinfunction "A_P$2") (pintype "passive"))
    )
    (net (code "68") (name "Net-(SOL4-+)") (class "Default")
      (node (ref "SOL4") (pin "P$2") (pinfunction "+_P$2") (pintype "bidirectional"))
      (node (ref "U$17") (pin "P$2") (pinfunction "A_P$2") (pintype "passive"))
    )
    (net (code "69") (name "Net-(STWD100PYW83F56-EN)") (class "Default")
      (node (ref "R24") (pin "2") (pinfunction "2_2") (pintype "passive"))
      (node (ref "SJ1") (pin "2") (pinfunction "2_2") (pintype "passive"))
      (node (ref "STWD100PYW83F56") (pin "3") (pinfunction "EN_3") (pintype "bidirectional"))
    )
    (net (code "70") (name "Net-(U$2-ILIM)") (class "Default")
      (node (ref "R17") (pin "2") (pinfunction "2_2") (pintype "passive"))
      (node (ref "U$2") (pin "12") (pinfunction "ILIM_12") (pintype "bidirectional"))
    )
    (net (code "71") (name "Net-(U$2-ISET)") (class "Default")
      (node (ref "R16") (pin "2") (pinfunction "2_2") (pintype "passive"))
      (node (ref "U$2") (pin "16") (pinfunction "ISET_16") (pintype "bidirectional"))
    )
    (net (code "72") (name "Net-(U$2-TS)") (class "Default")
      (node (ref "R15") (pin "2") (pinfunction "2_2") (pintype "passive"))
      (node (ref "U$2") (pin "1") (pinfunction "TS_1") (pintype "bidirectional"))
    )
    (net (code "73") (name "Net-(U$11-D)") (class "Default")
      (node (ref "R25") (pin "1") (pinfunction "1_1") (pintype "passive"))
      (node (ref "U$11") (pin "3") (pinfunction "D_3") (pintype "bidirectional"))
    )
    (net (code "74") (name "Net-(U$12-D)") (class "Default")
      (node (ref "R27") (pin "1") (pinfunction "1_1") (pintype "passive"))
      (node (ref "U$12") (pin "3") (pinfunction "D_3") (pintype "bidirectional"))
    )
    (net (code "75") (name "Net-(U$15-D)") (class "Default")
      (node (ref "R21") (pin "1") (pinfunction "1_1") (pintype "passive"))
      (node (ref "U$15") (pin "3") (pinfunction "D_3") (pintype "bidirectional"))
    )
    (net (code "76") (name "Net-(U$20-SNS)") (class "Default")
      (node (ref "R36") (pin "1") (pinfunction "1_1") (pintype "passive"))
      (node (ref "R37") (pin "1") (pinfunction "1_1") (pintype "passive"))
      (node (ref "U$20") (pin "P$1") (pinfunction "OUT_P$1") (pintype "bidirectional"))
      (node (ref "U$20") (pin "P$2") (pinfunction "OUT_P$2") (pintype "bidirectional"))
      (node (ref "U$20") (pin "P$4") (pinfunction "SNS_P$4") (pintype "bidirectional"))
      (node (ref "U$25") (pin "1") (pinfunction "VIN_1") (pintype "bidirectional"))
      (node (ref "U$26") (pin "1") (pinfunction "VIN_1") (pintype "bidirectional"))
    )
    (net (code "77") (name "Net-(U$21-PTB7)") (class "Default")
      (node (ref "TP1") (pin "TP") (pinfunction "TP_TP") (pintype "input"))
      (node (ref "U$21") (pin "2") (pinfunction "PTB7_2") (pintype "bidirectional"))
    )
    (net (code "78") (name "Net-(U9-ILIM)") (class "Default")
      (node (ref "R40") (pin "2") (pinfunction "2_2") (pintype "passive"))
      (node (ref "U9") (pin "2") (pinfunction "ILIM_2") (pintype "output"))
    )
    (net (code "79") (name "OPTO") (class "Default")
      (node (ref "R33") (pin "1") (pinfunction "1_1") (pintype "passive"))
      (node (ref "U$21") (pin "1") (pinfunction "PTB6_1") (pintype "bidirectional"))
    )
    (net (code "80") (name "SCK") (class "Default")
      (node (ref "PQ60_HEADER56") (pin "P$33") (pinfunction "SCK_P$33") (pintype "bidirectional"))
      (node (ref "PQ60_RECEPTACLE56") (pin "P$33") (pinfunction "SCK_P$33") (pintype "bidirectional"))
    )
    (net (code "81") (name "SCL") (class "Default")
      (node (ref "PQ60_HEADER56") (pin "P$29") (pinfunction "SCL_P$29") (pintype "bidirectional"))
      (node (ref "PQ60_RECEPTACLE56") (pin "P$29") (pinfunction "SCL_P$29") (pintype "bidirectional"))
      (node (ref "U$21") (pin "23") (pinfunction "PTB3_23") (pintype "bidirectional"))
    )
    (net (code "82") (name "SDA") (class "Default")
      (node (ref "PQ60_HEADER56") (pin "P$30") (pinfunction "SDA_P$30") (pintype "bidirectional"))
      (node (ref "PQ60_RECEPTACLE56") (pin "P$30") (pinfunction "SDA_P$30") (pintype "bidirectional"))
      (node (ref "U$21") (pin "24") (pinfunction "PTB4_24") (pintype "bidirectional"))
    )
    (net (code "83") (name "SHDN") (class "Default")
      (node (ref "U$10") (pin "P$1") (pinfunction "C_P$1") (pintype "passive"))
      (node (ref "U$24") (pin "COLLECTOR") (pinfunction "COLLECTOR_COLLECTOR") (pintype "bidirectional"))
      (node (ref "U$4") (pin "P$1") (pinfunction "C_P$1") (pintype "passive"))
    )
    (net (code "84") (name "SOL_ISEN") (class "Default")
      (node (ref "R8") (pin "2") (pinfunction "2_2") (pintype "passive"))
      (node (ref "U$18") (pin "3") (pinfunction "IOUT_3") (pintype "bidirectional"))
      (node (ref "U$21") (pin "13") (pinfunction "PTB10_13") (pintype "bidirectional"))
    )
    (net (code "85") (name "SWDCLK") (class "Default")
      (node (ref "U$21") (pin "30") (pinfunction "PTA0_30") (pintype "bidirectional"))
      (node (ref "U$22") (pin "4") (pinfunction "CLK_4") (pintype "bidirectional"))
      (node (ref "U$27") (pin "P$1") (pinfunction "P$1_P$1") (pintype "bidirectional"))
    )
    (net (code "86") (name "SWDIO") (class "Default")
      (node (ref "U$21") (pin "32") (pinfunction "PTA2_32") (pintype "bidirectional"))
      (node (ref "U$22") (pin "2") (pinfunction "DIO_2") (pintype "bidirectional"))
      (node (ref "U$28") (pin "P$1") (pinfunction "P$1_P$1") (pintype "bidirectional"))
    )
    (net (code "87") (name "SWDRST") (class "Default")
      (node (ref "U$16") (pin "P$1") (pinfunction "P$1_P$1") (pintype "bidirectional"))
      (node (ref "U$21") (pin "31") (pinfunction "PTA1_31") (pintype "bidirectional"))
      (node (ref "U$22") (pin "3") (pinfunction "RST_3") (pintype "bidirectional"))
    )
    (net (code "88") (name "SYS") (class "Default")
      (node (ref "PWR56") (pin "PIN2") (pinfunction "PIN2_PIN2") (pintype "bidirectional"))
      (node (ref "U$2") (pin "10") (pinfunction "OUT_10") (pintype "bidirectional"))
      (node (ref "U$2") (pin "11") (pinfunction "OUT_11") (pintype "bidirectional"))
    )
    (net (code "89") (name "SYS_RAW") (class "Default")
      (node (ref "SJ1") (pin "1") (pinfunction "1_1") (pintype "passive"))
      (node (ref "U$20") (pin "P$7") (pinfunction "IN_P$7") (pintype "bidirectional"))
      (node (ref "U$20") (pin "P$8") (pinfunction "IN_P$8") (pintype "bidirectional"))
      (node (ref "U9") (pin "1") (pinfunction "OUT_1") (pintype "output"))
    )
    (net (code "90") (name "SYS_SW") (class "Default")
      (node (ref "BU4331G-TR56") (pin "2") (pinfunction "VDD_2") (pintype "bidirectional"))
      (node (ref "C22") (pin "1") (pinfunction "1_1") (pintype "passive"))
      (node (ref "PWR56") (pin "PIN1") (pinfunction "PIN1_PIN1") (pintype "bidirectional"))
      (node (ref "R28") (pin "2") (pinfunction "2_2") (pintype "passive"))
      (node (ref "STWD100PYW83F56") (pin "5") (pinfunction "VCC_5") (pintype "bidirectional"))
      (node (ref "U9") (pin "6") (pinfunction "IN_6") (pintype "power_in"))
    )
    (net (code "91") (name "USB_DISCONNECT") (class "Default")
      (node (ref "R30") (pin "1") (pinfunction "1_1") (pintype "passive"))
      (node (ref "U$21") (pin "9") (pinfunction "PTA5_9") (pintype "bidirectional"))
      (node (ref "U12") (pin "2") (pinfunction "ON1_2") (pintype "input"))
    )
    (net (code "92") (name "WDI") (class "Default")
      (node (ref "STWD100PYW83F56") (pin "4") (pinfunction "WDI_4") (pintype "bidirectional"))
      (node (ref "U$21") (pin "10") (pinfunction "PTA6_10") (pintype "bidirectional"))
    )
    (net (code "93") (name "XTAL") (class "Default")
      (node (ref "U$21") (pin "8") (pinfunction "PTA4_8") (pintype "bidirectional"))
      (node (ref "U$8") (pin "4") (pinfunction "P$2_4") (pintype "bidirectional"))
    )
    (net (code "94") (name "unconnected-(BU4331G-TR56-NC-Pad4)") (class "Default")
      (node (ref "BU4331G-TR56") (pin "4") (pinfunction "NC_4") (pintype "bidirectional"))
    )
    (net (code "95") (name "unconnected-(MPPT1-PGOOD-Pad8)") (class "Default")
      (node (ref "MPPT1") (pin "8") (pinfunction "PGOOD_8") (pintype "passive"))
    )
    (net (code "96") (name "unconnected-(MPPT2-PGOOD-Pad8)") (class "Default")
      (node (ref "MPPT2") (pin "8") (pinfunction "PGOOD_8") (pintype "passive"))
    )
    (net (code "97") (name "unconnected-(U$18-NC-Pad2)") (class "Default")
      (node (ref "U$18") (pin "2") (pinfunction "NC_2") (pintype "bidirectional"))
    )
    (net (code "98") (name "unconnected-(U$18-NC-Pad4)") (class "Default")
      (node (ref "U$18") (pin "4") (pinfunction "NC_4") (pintype "bidirectional"))
    )
    (net (code "99") (name "unconnected-(U$19-NC-Pad2)") (class "Default")
      (node (ref "U$19") (pin "2") (pinfunction "NC_2") (pintype "bidirectional"))
    )
    (net (code "100") (name "unconnected-(U$19-NC-Pad4)") (class "Default")
      (node (ref "U$19") (pin "4") (pinfunction "NC_4") (pintype "bidirectional"))
    )
    (net (code "101") (name "unconnected-(U$20-N{slash}C-PadP$3)") (class "Default")
      (node (ref "U$20") (pin "P$3") (pinfunction "N/C_P$3") (pintype "bidirectional"))
    )
    (net (code "102") (name "unconnected-(U$21-PTB13-Pad29)") (class "Default")
      (node (ref "U$21") (pin "29") (pinfunction "PTB13_29") (pintype "bidirectional"))
    )
    (net (code "103") (name "unconnected-(U$22-SWO-Pad6)") (class "Default")
      (node (ref "U$22") (pin "6") (pinfunction "SWO_6") (pintype "bidirectional"))
    )
    (net (code "104") (name "unconnected-(U$25-NC-Pad2)") (class "Default")
      (node (ref "U$25") (pin "2") (pinfunction "NC_2") (pintype "bidirectional"))
    )
    (net (code "105") (name "unconnected-(U$25-NC-Pad4)") (class "Default")
      (node (ref "U$25") (pin "4") (pinfunction "NC_4") (pintype "bidirectional"))
    )
    (net (code "106") (name "unconnected-(U$26-NC-Pad2)") (class "Default")
      (node (ref "U$26") (pin "2") (pinfunction "NC_2") (pintype "bidirectional"))
    )
    (net (code "107") (name "unconnected-(U$26-NC-Pad4)") (class "Default")
      (node (ref "U$26") (pin "4") (pinfunction "NC_4") (pintype "bidirectional"))
    )
    (net (code "108") (name "unconnected-(U1-NC-Pad7)") (class "Default")
      (node (ref "U1") (pin "7") (pinfunction "NC_7") (pintype "no_connect"))
    )
    (net (code "109") (name "unconnected-(U1-NC_2-Pad8)") (class "Default")
      (node (ref "U1") (pin "8") (pinfunction "NC_2_8") (pintype "no_connect"))
    )
    (net (code "110") (name "unconnected-(U9-~{FAULT}-Pad3)") (class "Default")
      (node (ref "U9") (pin "3") (pinfunction "~{FAULT}_3") (pintype "output"))
    )
    (net (code "111") (name "unconnected-(U10-SR-Pad7)") (class "Default")
      (node (ref "U10") (pin "7") (pinfunction "SR_7") (pintype "input"))
    )
    (net (code "112") (name "unconnected-(U11-SR-Pad7)") (class "Default")
      (node (ref "U11") (pin "7") (pinfunction "SR_7") (pintype "input"))
    )
    (net (code "113") (name "unconnected-(U12-SR-Pad7)") (class "Default")
      (node (ref "U12") (pin "7") (pinfunction "SR_7") (pintype "input"))
    )
  )
)
